# Connectors.net
KiCad netlist of a schematic drawn in Altium Designer
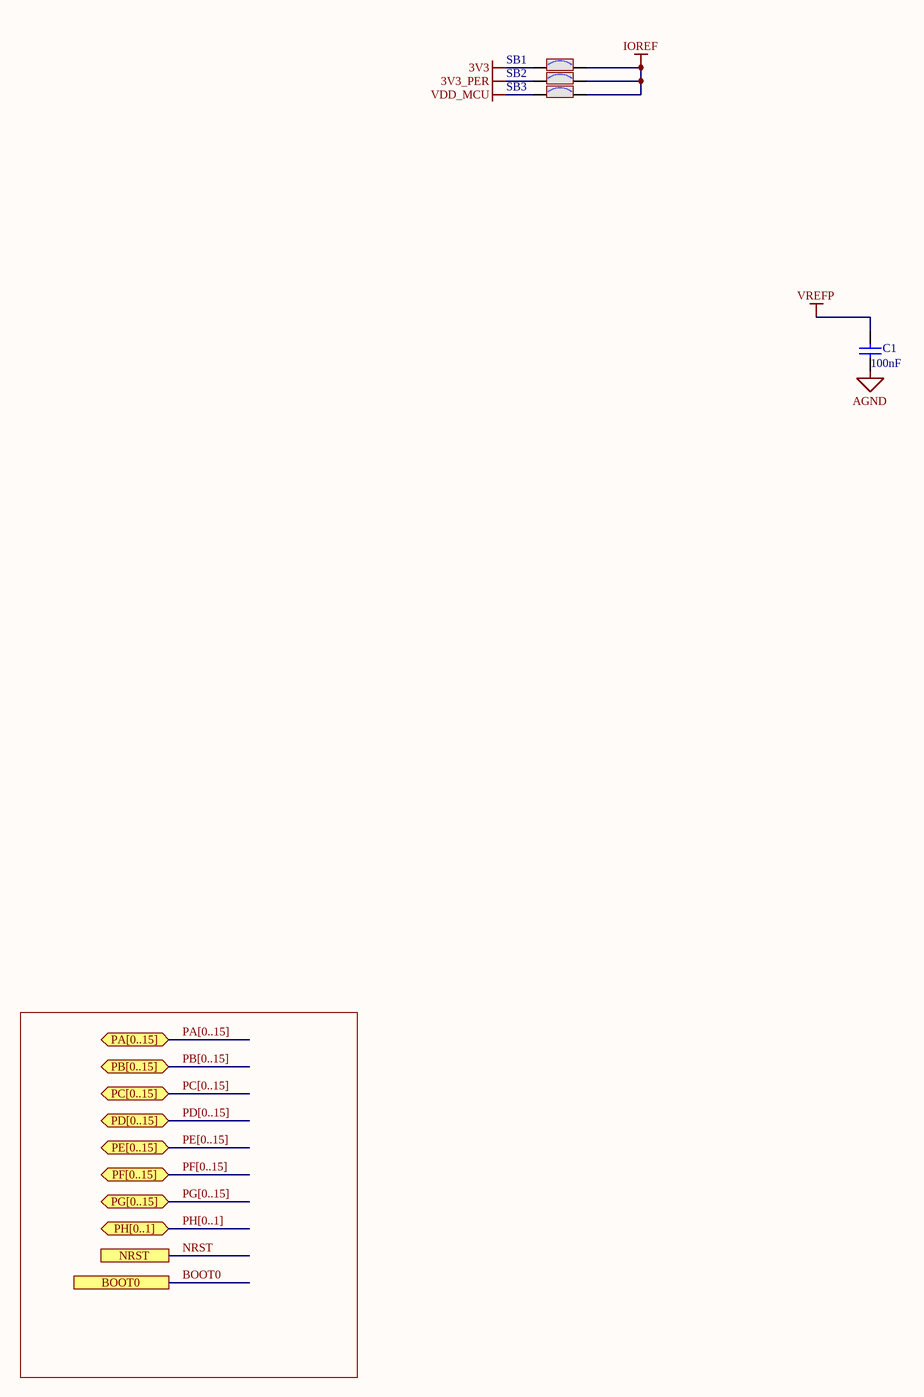
[diagram p0: Connectors.SchDoc]

(export (version "E")
  (design (tool "Eeschema 10.0.6"))
  (components
    (comp (ref "C1")
      (value "Capacitor")
      (footprint "C0402")
      (description "CAP CER 0.1UF 16V X7R 0402")
      (fields
        (field (name "MANUFACTURER") "Yageo")
        (field (name "MANUFACTURER PART NUMBER") "CC0402KRX7R7BB104")
        (field (name "CAPACITANCE") "100nF")
      )
      (libsource (lib "MCD_PARTS_database") (part "Capacitor"))
    )
    (comp (ref "SB1")
      (value "SB_ON")
      (footprint "SOLDER-BRIDGE_R0603-0R")
      (description "Solder Bridge ON")
      (fields
        (field (name "INTERNAL_PART_NUMBER") "MCD-00071")
        (field (name "MANUFACTURER_PART_NUMBER") "RC0603JR-070RL")
        (field (name "PROVIDED_BY") "SUBCO")
      )
      (libsource (lib "MCD_PARTS_database") (part "SB_ON"))
    )
    (comp (ref "SB2")
      (value "SB_ON")
      (footprint "SOLDER-BRIDGE_R0603-0R")
      (description "Solder Bridge ON")
      (fields
        (field (name "INTERNAL_PART_NUMBER") "MCD-00071")
        (field (name "MANUFACTURER_PART_NUMBER") "RC0603JR-070RL")
        (field (name "PROVIDED_BY") "SUBCO")
      )
      (libsource (lib "MCD_PARTS_database") (part "SB_ON"))
    )
    (comp (ref "SB3")
      (value "SB_ON")
      (footprint "SOLDER-BRIDGE_R0603-0R")
      (description "Solder Bridge ON")
      (fields
        (field (name "INTERNAL_PART_NUMBER") "MCD-00071")
        (field (name "MANUFACTURER_PART_NUMBER") "RC0603JR-070RL")
        (field (name "PROVIDED_BY") "SUBCO")
      )
      (libsource (lib "MCD_PARTS_database") (part "SB_ON"))
    )
  )
  (nets
    (net (code "125") (name "3V3") (class "Default")
      (node (ref "SB1") (pin "1") (pinfunction "1_1") (pintype "passive"))
    )
    (net (code "126") (name "3V3_PER") (class "Default")
      (node (ref "SB2") (pin "1") (pinfunction "1_1") (pintype "passive"))
    )
    (net (code "127") (name "AGND") (class "Default")
      (node (ref "C1") (pin "1") (pinfunction "1_1") (pintype "passive"))
    )
    (net (code "128") (name "IOREF") (class "Default")
      (node (ref "SB1") (pin "2") (pinfunction "2_2") (pintype "passive"))
      (node (ref "SB2") (pin "2") (pinfunction "2_2") (pintype "passive"))
      (node (ref "SB3") (pin "2") (pinfunction "2_2") (pintype "passive"))
    )
    (net (code "129") (name "VDD_MCU") (class "Default")
      (node (ref "SB3") (pin "1") (pinfunction "1_1") (pintype "passive"))
    )
    (net (code "130") (name "VREFP") (class "Default")
      (node (ref "C1") (pin "2") (pinfunction "2_2") (pintype "passive"))
    )
  )
)
